# infinity_mirror_revd.net
KiCad netlist of a schematic drawn in EAGLE
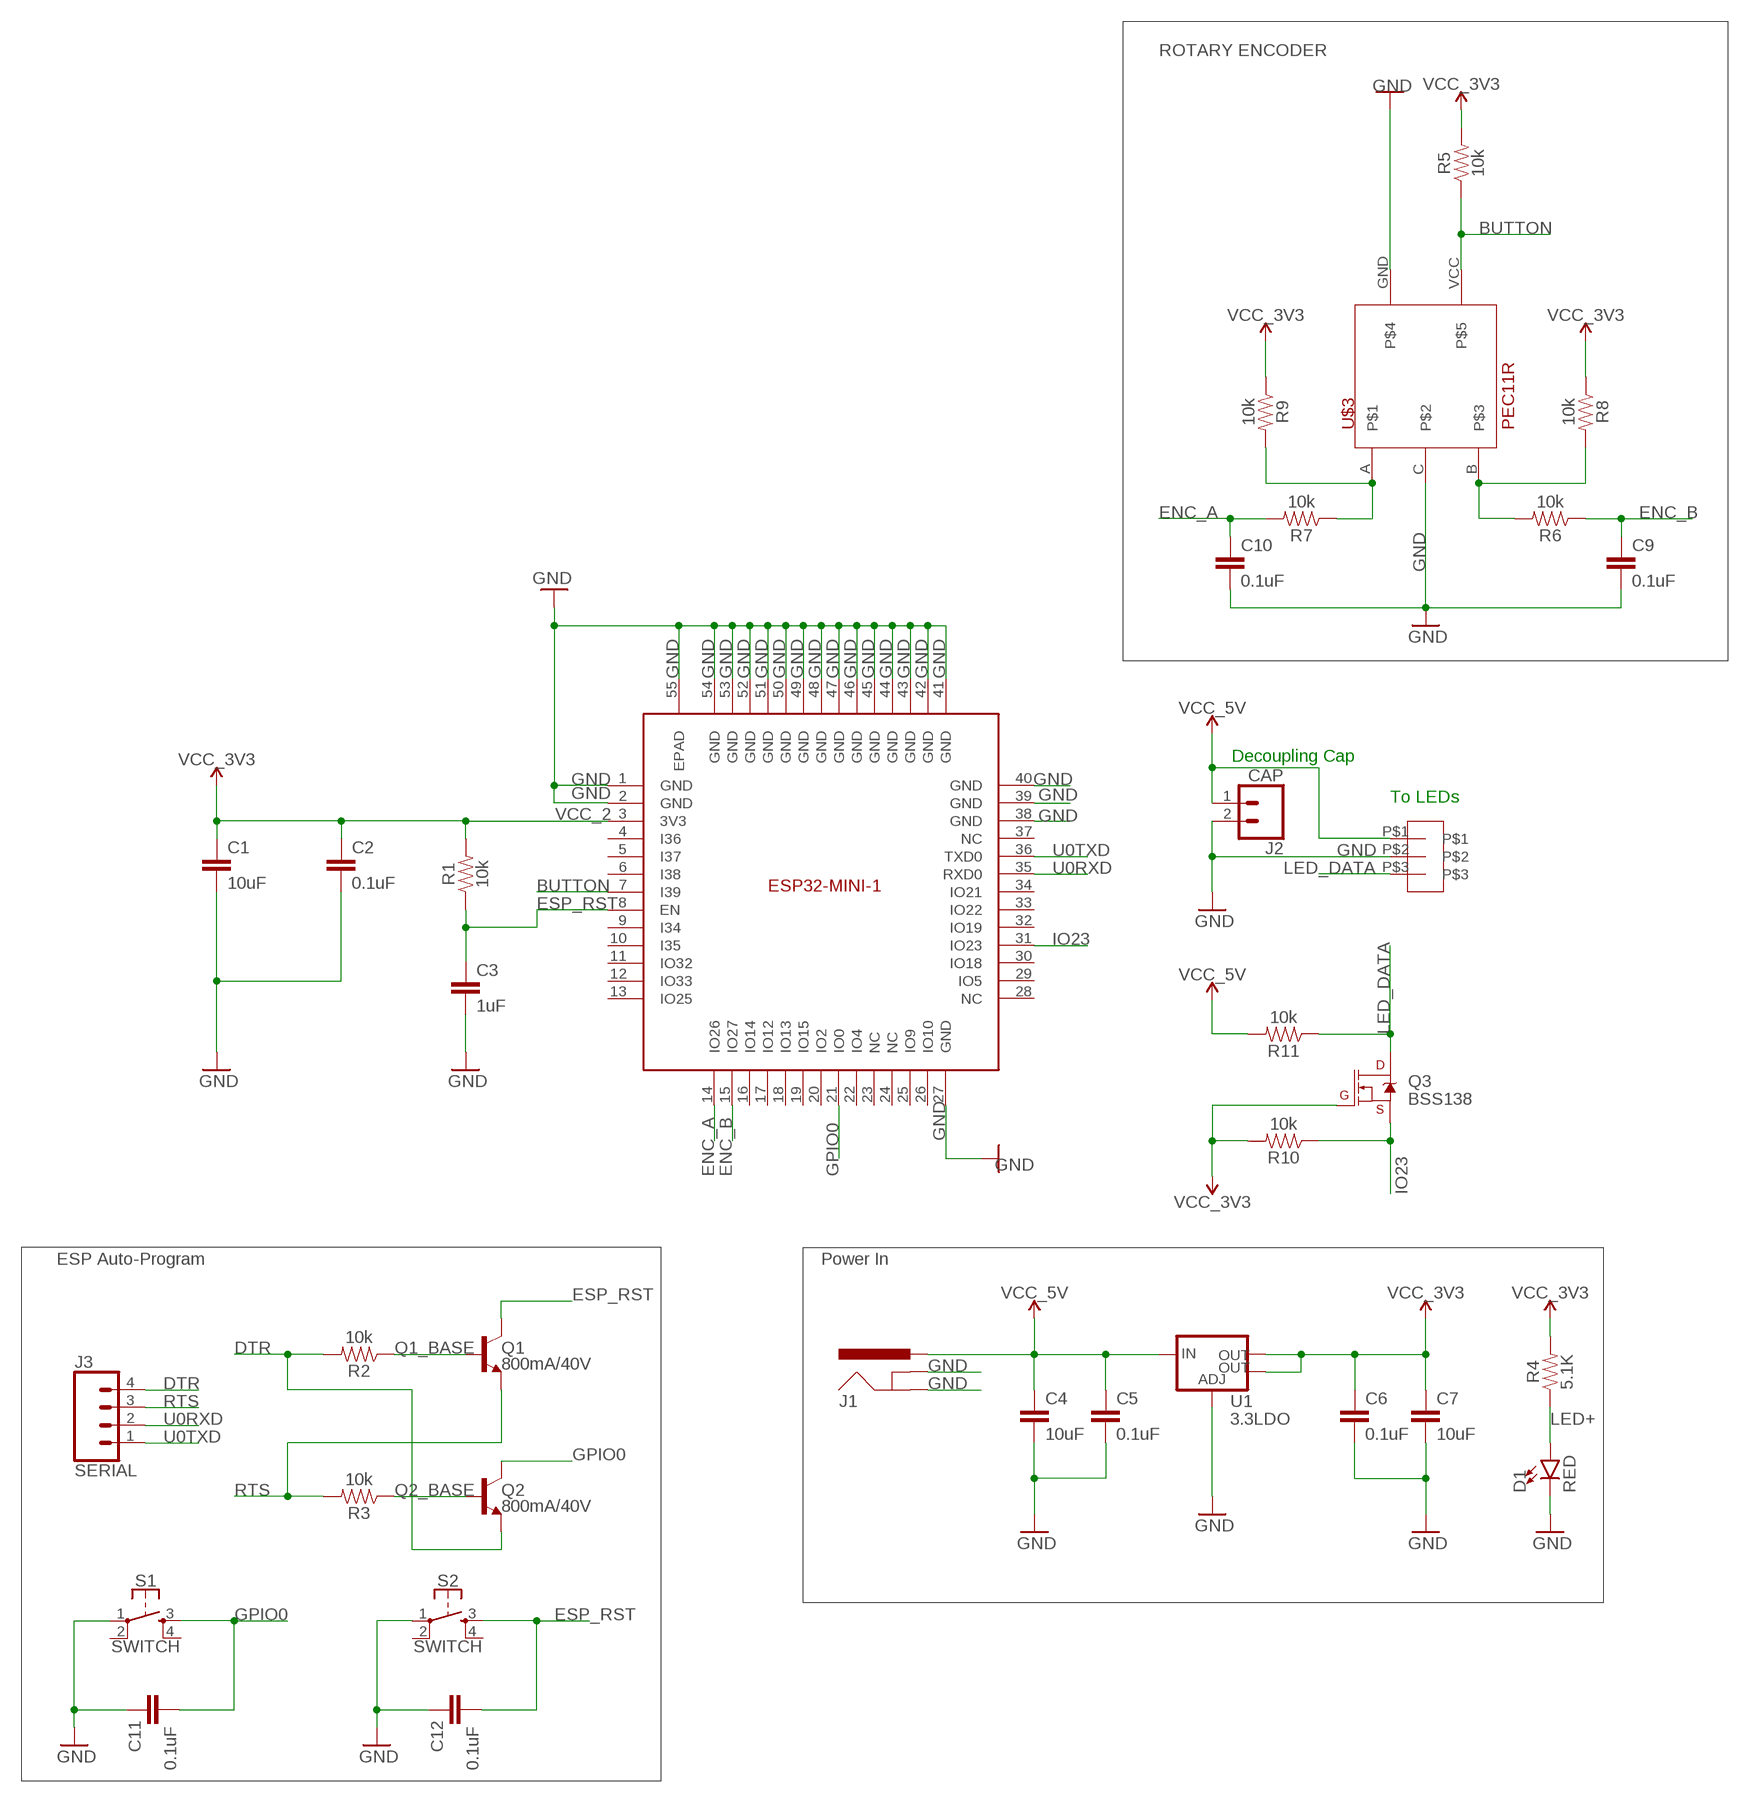
[diagram p0: schematic, sheet 1]

(export (version "E")
  (design (tool "Eeschema 10.0.6"))
  (components
    (comp (ref "C1")
      (value "10uF")
      (footprint "eagle-import:0805")
      (libsource (lib "eagle-import") (part "CAPACITOR"))
    )
    (comp (ref "C2")
      (value "0.1uF")
      (footprint "eagle-import:0805")
      (libsource (lib "eagle-import") (part "CAPACITOR"))
    )
    (comp (ref "C3")
      (value "1uF")
      (footprint "eagle-import:0805")
      (libsource (lib "eagle-import") (part "CAPACITOR"))
    )
    (comp (ref "C4")
      (value "10uF")
      (footprint "eagle-import:0805")
      (libsource (lib "eagle-import") (part "CAPACITOR"))
    )
    (comp (ref "C5")
      (value "0.1uF")
      (footprint "eagle-import:0805")
      (libsource (lib "eagle-import") (part "CAPACITOR"))
    )
    (comp (ref "C6")
      (value "0.1uF")
      (footprint "eagle-import:0805")
      (libsource (lib "eagle-import") (part "CAPACITOR"))
    )
    (comp (ref "C7")
      (value "10uF")
      (footprint "eagle-import:0805")
      (libsource (lib "eagle-import") (part "CAPACITOR"))
    )
    (comp (ref "C9")
      (value "0.1uF")
      (footprint "eagle-import:0805")
      (libsource (lib "eagle-import") (part "CAPACITOR"))
    )
    (comp (ref "C10")
      (value "0.1uF")
      (footprint "eagle-import:0805")
      (libsource (lib "eagle-import") (part "CAPACITOR"))
    )
    (comp (ref "C11")
      (value "0.1uF")
      (footprint "eagle-import:0805")
      (libsource (lib "eagle-import") (part "CAPACITOR"))
    )
    (comp (ref "C12")
      (value "0.1uF")
      (footprint "eagle-import:0805")
      (libsource (lib "eagle-import") (part "CAPACITOR"))
    )
    (comp (ref "D1")
      (value "RED")
      (footprint "eagle-import:LED-1206")
      (libsource (lib "eagle-import") (part "LED-RED1206"))
    )
    (comp (ref "J1")
      (value "POWER_JACKPTH_BREAD")
      (footprint "eagle-import:POWER_JACK_PTH_BREAD")
      (libsource (lib "eagle-import") (part "POWER_JACKPTH_BREAD"))
    )
    (comp (ref "J2")
      (value "CAP")
      (footprint "eagle-import:1X02")
      (libsource (lib "eagle-import") (part "CONN_02"))
    )
    (comp (ref "J3")
      (value "SERIAL")
      (footprint "eagle-import:1X04")
      (libsource (lib "eagle-import") (part "CONN_04"))
    )
    (comp (ref "Q1")
      (value "800mA/40V")
      (footprint "eagle-import:SOT23-3")
      (libsource (lib "eagle-import") (part "TRANS_NPN-MMBT2222AL"))
    )
    (comp (ref "Q2")
      (value "800mA/40V")
      (footprint "eagle-import:SOT23-3")
      (libsource (lib "eagle-import") (part "TRANS_NPN-MMBT2222AL"))
    )
    (comp (ref "Q3")
      (value "BSS138")
      (footprint "eagle-import:SOT23-3")
      (libsource (lib "eagle-import") (part "MOSFET-NCH-BSS138"))
    )
    (comp (ref "R1")
      (value "10k")
      (footprint "eagle-import:0805")
      (libsource (lib "eagle-import") (part "RESISTOR"))
    )
    (comp (ref "R2")
      (value "10k")
      (footprint "eagle-import:0805")
      (libsource (lib "eagle-import") (part "RESISTOR"))
    )
    (comp (ref "R3")
      (value "10k")
      (footprint "eagle-import:0805")
      (libsource (lib "eagle-import") (part "RESISTOR"))
    )
    (comp (ref "R4")
      (value "5.1K")
      (footprint "eagle-import:0805")
      (libsource (lib "eagle-import") (part "RESISTOR"))
    )
    (comp (ref "R5")
      (value "10k")
      (footprint "eagle-import:0805")
      (libsource (lib "eagle-import") (part "RESISTOR"))
    )
    (comp (ref "R6")
      (value "10k")
      (footprint "eagle-import:0805")
      (libsource (lib "eagle-import") (part "RESISTOR"))
    )
    (comp (ref "R7")
      (value "10k")
      (footprint "eagle-import:0805")
      (libsource (lib "eagle-import") (part "RESISTOR"))
    )
    (comp (ref "R8")
      (value "10k")
      (footprint "eagle-import:0805")
      (libsource (lib "eagle-import") (part "RESISTOR"))
    )
    (comp (ref "R9")
      (value "10k")
      (footprint "eagle-import:0805")
      (libsource (lib "eagle-import") (part "RESISTOR"))
    )
    (comp (ref "R10")
      (value "10k")
      (footprint "eagle-import:0805")
      (libsource (lib "eagle-import") (part "RESISTOR"))
    )
    (comp (ref "R11")
      (value "10k")
      (footprint "eagle-import:0805")
      (libsource (lib "eagle-import") (part "RESISTOR"))
    )
    (comp (ref "S1")
      (value "SWITCH")
      (footprint "eagle-import:TACTILE_SWITCH_SMD_5.2MM")
      (libsource (lib "eagle-import") (part "MOMENTARY-SWITCH-SPST-2-SMD-5.2MM-TALL"))
    )
    (comp (ref "S2")
      (value "SWITCH")
      (footprint "eagle-import:TACTILE_SWITCH_SMD_5.2MM")
      (libsource (lib "eagle-import") (part "MOMENTARY-SWITCH-SPST-2-SMD-5.2MM-TALL"))
    )
    (comp (ref "U$1")
      (value "ESP32-MINI-1-N4")
      (footprint "eagle-import:ESP32-MINI-1-N4")
      (libsource (lib "eagle-import") (part "ESP32-MINI-1-N4"))
    )
    (comp (ref "U$2")
      (value "3-PIN-JST")
      (footprint "eagle-import:3-PIN-JST")
      (libsource (lib "eagle-import") (part "3-PIN-JST"))
    )
    (comp (ref "U$3")
      (value "PEC11R")
      (footprint "eagle-import:PEC11R-4320F-S0012")
      (libsource (lib "eagle-import") (part "PEC11R_ROTARY_ENCODER"))
    )
    (comp (ref "U1")
      (value "3.3LDO")
      (footprint "eagle-import:SOT223")
      (libsource (lib "eagle-import") (part "V_REG_LM1117SOT223"))
    )
  )
  (nets
    (net (code "1") (name "/BUTTON") (class "Default")
      (node (ref "R5") (pin "1") (pinfunction "1_1") (pintype "passive"))
      (node (ref "U$1") (pin "7") (pinfunction "I39_7") (pintype "bidirectional"))
      (node (ref "U$3") (pin "VCC") (pinfunction "P$5_VCC") (pintype "bidirectional"))
    )
    (net (code "2") (name "/DTR") (class "Default")
      (node (ref "J3") (pin "4") (pinfunction "4_4") (pintype "passive"))
      (node (ref "Q2") (pin "2") (pinfunction "E_2") (pintype "passive"))
      (node (ref "R2") (pin "2") (pinfunction "2_2") (pintype "passive"))
    )
    (net (code "3") (name "/ENC_A") (class "Default")
      (node (ref "C10") (pin "1") (pinfunction "1_1") (pintype "passive"))
      (node (ref "R7") (pin "2") (pinfunction "2_2") (pintype "passive"))
      (node (ref "U$1") (pin "14") (pinfunction "IO26_14") (pintype "bidirectional"))
    )
    (net (code "4") (name "/ENC_B") (class "Default")
      (node (ref "C9") (pin "1") (pinfunction "1_1") (pintype "passive"))
      (node (ref "R6") (pin "1") (pinfunction "1_1") (pintype "passive"))
      (node (ref "U$1") (pin "15") (pinfunction "IO27_15") (pintype "bidirectional"))
    )
    (net (code "5") (name "/ESP_RST") (class "Default")
      (node (ref "C12") (pin "2") (pinfunction "2_2") (pintype "passive"))
      (node (ref "C3") (pin "1") (pinfunction "1_1") (pintype "passive"))
      (node (ref "Q1") (pin "3") (pinfunction "C_3") (pintype "passive"))
      (node (ref "R1") (pin "1") (pinfunction "1_1") (pintype "passive"))
      (node (ref "S2") (pin "3") (pinfunction "3_3") (pintype "passive"))
      (node (ref "U$1") (pin "8") (pinfunction "EN_8") (pintype "bidirectional"))
    )
    (net (code "6") (name "/GPIO0") (class "Default")
      (node (ref "C11") (pin "2") (pinfunction "2_2") (pintype "passive"))
      (node (ref "Q2") (pin "3") (pinfunction "C_3") (pintype "passive"))
      (node (ref "S1") (pin "3") (pinfunction "3_3") (pintype "passive"))
      (node (ref "U$1") (pin "21") (pinfunction "IO0_21") (pintype "bidirectional"))
    )
    (net (code "7") (name "/IO23") (class "Default")
      (node (ref "Q3") (pin "2") (pinfunction "S_2") (pintype "bidirectional"))
      (node (ref "R10") (pin "1") (pinfunction "1_1") (pintype "passive"))
      (node (ref "U$1") (pin "31") (pinfunction "IO23_31") (pintype "bidirectional"))
    )
    (net (code "8") (name "/LED+") (class "Default")
      (node (ref "D1") (pin "A") (pinfunction "A_A") (pintype "passive"))
      (node (ref "R4") (pin "1") (pinfunction "1_1") (pintype "passive"))
    )
    (net (code "9") (name "/LED_DATA") (class "Default")
      (node (ref "Q3") (pin "3") (pinfunction "D_3") (pintype "bidirectional"))
      (node (ref "R11") (pin "1") (pinfunction "1_1") (pintype "passive"))
      (node (ref "U$2") (pin "P$3") (pinfunction "P$3_P$3") (pintype "bidirectional"))
    )
    (net (code "10") (name "/Q1_BASE") (class "Default")
      (node (ref "Q1") (pin "1") (pinfunction "B_1") (pintype "passive"))
      (node (ref "R2") (pin "1") (pinfunction "1_1") (pintype "passive"))
    )
    (net (code "11") (name "/Q2_BASE") (class "Default")
      (node (ref "Q2") (pin "1") (pinfunction "B_1") (pintype "passive"))
      (node (ref "R3") (pin "1") (pinfunction "1_1") (pintype "passive"))
    )
    (net (code "12") (name "/RTS") (class "Default")
      (node (ref "J3") (pin "3") (pinfunction "3_3") (pintype "passive"))
      (node (ref "Q1") (pin "2") (pinfunction "E_2") (pintype "passive"))
      (node (ref "R3") (pin "2") (pinfunction "2_2") (pintype "passive"))
    )
    (net (code "13") (name "/U0RXD") (class "Default")
      (node (ref "J3") (pin "2") (pinfunction "2_2") (pintype "passive"))
      (node (ref "U$1") (pin "35") (pinfunction "RXD0_35") (pintype "bidirectional"))
    )
    (net (code "14") (name "/U0TXD") (class "Default")
      (node (ref "J3") (pin "1") (pinfunction "1_1") (pintype "passive"))
      (node (ref "U$1") (pin "36") (pinfunction "TXD0_36") (pintype "bidirectional"))
    )
    (net (code "15") (name "GND") (class "Default")
      (node (ref "C1") (pin "2") (pinfunction "2_2") (pintype "passive"))
      (node (ref "C10") (pin "2") (pinfunction "2_2") (pintype "passive"))
      (node (ref "C11") (pin "1") (pinfunction "1_1") (pintype "passive"))
      (node (ref "C12") (pin "1") (pinfunction "1_1") (pintype "passive"))
      (node (ref "C2") (pin "2") (pinfunction "2_2") (pintype "passive"))
      (node (ref "C3") (pin "2") (pinfunction "2_2") (pintype "passive"))
      (node (ref "C4") (pin "2") (pinfunction "2_2") (pintype "passive"))
      (node (ref "C5") (pin "2") (pinfunction "2_2") (pintype "passive"))
      (node (ref "C6") (pin "2") (pinfunction "2_2") (pintype "passive"))
      (node (ref "C7") (pin "2") (pinfunction "2_2") (pintype "passive"))
      (node (ref "C9") (pin "2") (pinfunction "2_2") (pintype "passive"))
      (node (ref "D1") (pin "C") (pinfunction "C_C") (pintype "passive"))
      (node (ref "J1") (pin "GND") (pinfunction "GND_GND") (pintype "bidirectional"))
      (node (ref "J1") (pin "GNDBREAK") (pinfunction "GNDBREAK_GNDBREAK") (pintype "bidirectional"))
      (node (ref "J2") (pin "2") (pinfunction "2_2") (pintype "passive"))
      (node (ref "S1") (pin "1") (pinfunction "1_1") (pintype "passive"))
      (node (ref "S2") (pin "1") (pinfunction "1_1") (pintype "passive"))
      (node (ref "U$1") (pin "1") (pinfunction "GND_1") (pintype "bidirectional"))
      (node (ref "U$1") (pin "2") (pinfunction "GND_2") (pintype "bidirectional"))
      (node (ref "U$1") (pin "27") (pinfunction "GND_27") (pintype "bidirectional"))
      (node (ref "U$1") (pin "38") (pinfunction "GND_38") (pintype "bidirectional"))
      (node (ref "U$1") (pin "39") (pinfunction "GND_39") (pintype "bidirectional"))
      (node (ref "U$1") (pin "40") (pinfunction "GND_40") (pintype "bidirectional"))
      (node (ref "U$1") (pin "41") (pinfunction "GND_41") (pintype "bidirectional"))
      (node (ref "U$1") (pin "42") (pinfunction "GND_42") (pintype "bidirectional"))
      (node (ref "U$1") (pin "43") (pinfunction "GND_43") (pintype "bidirectional"))
      (node (ref "U$1") (pin "44") (pinfunction "GND_44") (pintype "bidirectional"))
      (node (ref "U$1") (pin "45") (pinfunction "GND_45") (pintype "bidirectional"))
      (node (ref "U$1") (pin "46") (pinfunction "GND_46") (pintype "bidirectional"))
      (node (ref "U$1") (pin "47") (pinfunction "GND_47") (pintype "bidirectional"))
      (node (ref "U$1") (pin "48") (pinfunction "GND_48") (pintype "bidirectional"))
      (node (ref "U$1") (pin "49") (pinfunction "GND_49") (pintype "bidirectional"))
      (node (ref "U$1") (pin "50") (pinfunction "GND_50") (pintype "bidirectional"))
      (node (ref "U$1") (pin "51") (pinfunction "GND_51") (pintype "bidirectional"))
      (node (ref "U$1") (pin "52") (pinfunction "GND_52") (pintype "bidirectional"))
      (node (ref "U$1") (pin "53") (pinfunction "GND_53") (pintype "bidirectional"))
      (node (ref "U$1") (pin "54") (pinfunction "GND_54") (pintype "bidirectional"))
      (node (ref "U$1") (pin "55") (pinfunction "EPAD_55") (pintype "bidirectional"))
      (node (ref "U$2") (pin "P$2") (pinfunction "P$2_P$2") (pintype "bidirectional"))
      (node (ref "U$3") (pin "C") (pinfunction "P$2_C") (pintype "bidirectional"))
      (node (ref "U$3") (pin "GND") (pinfunction "P$4_GND") (pintype "bidirectional"))
      (node (ref "U1") (pin "1") (pinfunction "ADJ_1") (pintype "input"))
    )
    (net (code "16") (name "Net-(U$3-P$1)") (class "Default")
      (node (ref "R7") (pin "1") (pinfunction "1_1") (pintype "passive"))
      (node (ref "R9") (pin "2") (pinfunction "2_2") (pintype "passive"))
      (node (ref "U$3") (pin "A") (pinfunction "P$1_A") (pintype "bidirectional"))
    )
    (net (code "17") (name "Net-(U$3-P$3)") (class "Default")
      (node (ref "R6") (pin "2") (pinfunction "2_2") (pintype "passive"))
      (node (ref "R8") (pin "2") (pinfunction "2_2") (pintype "passive"))
      (node (ref "U$3") (pin "B") (pinfunction "P$3_B") (pintype "bidirectional"))
    )
    (net (code "18") (name "VCC_3V3") (class "Default")
      (node (ref "C1") (pin "1") (pinfunction "1_1") (pintype "passive"))
      (node (ref "C2") (pin "1") (pinfunction "1_1") (pintype "passive"))
      (node (ref "C6") (pin "1") (pinfunction "1_1") (pintype "passive"))
      (node (ref "C7") (pin "1") (pinfunction "1_1") (pintype "passive"))
      (node (ref "Q3") (pin "1") (pinfunction "G_1") (pintype "bidirectional"))
      (node (ref "R1") (pin "2") (pinfunction "2_2") (pintype "passive"))
      (node (ref "R10") (pin "2") (pinfunction "2_2") (pintype "passive"))
      (node (ref "R4") (pin "2") (pinfunction "2_2") (pintype "passive"))
      (node (ref "R5") (pin "2") (pinfunction "2_2") (pintype "passive"))
      (node (ref "R8") (pin "1") (pinfunction "1_1") (pintype "passive"))
      (node (ref "R9") (pin "1") (pinfunction "1_1") (pintype "passive"))
      (node (ref "U$1") (pin "3") (pinfunction "3V3_3") (pintype "bidirectional"))
      (node (ref "U1") (pin "2") (pinfunction "OUT_2") (pintype "output"))
      (node (ref "U1") (pin "4") (pinfunction "OUT_4") (pintype "output"))
    )
    (net (code "19") (name "VCC_5V") (class "Default")
      (node (ref "C4") (pin "1") (pinfunction "1_1") (pintype "passive"))
      (node (ref "C5") (pin "1") (pinfunction "1_1") (pintype "passive"))
      (node (ref "J1") (pin "PWR") (pinfunction "PWR_PWR") (pintype "bidirectional"))
      (node (ref "J2") (pin "1") (pinfunction "1_1") (pintype "passive"))
      (node (ref "R11") (pin "2") (pinfunction "2_2") (pintype "passive"))
      (node (ref "U$2") (pin "P$1") (pinfunction "P$1_P$1") (pintype "bidirectional"))
      (node (ref "U1") (pin "3") (pinfunction "IN_3") (pintype "input"))
    )
    (net (code "20") (name "unconnected-(S1-Pad2)") (class "Default")
      (node (ref "S1") (pin "2") (pinfunction "2_2") (pintype "passive"))
    )
    (net (code "21") (name "unconnected-(S1-Pad4)") (class "Default")
      (node (ref "S1") (pin "4") (pinfunction "4_4") (pintype "passive"))
    )
    (net (code "22") (name "unconnected-(S2-Pad2)") (class "Default")
      (node (ref "S2") (pin "2") (pinfunction "2_2") (pintype "passive"))
    )
    (net (code "23") (name "unconnected-(S2-Pad4)") (class "Default")
      (node (ref "S2") (pin "4") (pinfunction "4_4") (pintype "passive"))
    )
    (net (code "24") (name "unconnected-(U$1-I34-Pad9)") (class "Default")
      (node (ref "U$1") (pin "9") (pinfunction "I34_9") (pintype "bidirectional"))
    )
    (net (code "25") (name "unconnected-(U$1-I35-Pad10)") (class "Default")
      (node (ref "U$1") (pin "10") (pinfunction "I35_10") (pintype "bidirectional"))
    )
    (net (code "26") (name "unconnected-(U$1-I36-Pad4)") (class "Default")
      (node (ref "U$1") (pin "4") (pinfunction "I36_4") (pintype "bidirectional"))
    )
    (net (code "27") (name "unconnected-(U$1-I37-Pad5)") (class "Default")
      (node (ref "U$1") (pin "5") (pinfunction "I37_5") (pintype "bidirectional"))
    )
    (net (code "28") (name "unconnected-(U$1-I38-Pad6)") (class "Default")
      (node (ref "U$1") (pin "6") (pinfunction "I38_6") (pintype "bidirectional"))
    )
    (net (code "29") (name "unconnected-(U$1-IO2-Pad20)") (class "Default")
      (node (ref "U$1") (pin "20") (pinfunction "IO2_20") (pintype "bidirectional"))
    )
    (net (code "30") (name "unconnected-(U$1-IO4-Pad22)") (class "Default")
      (node (ref "U$1") (pin "22") (pinfunction "IO4_22") (pintype "bidirectional"))
    )
    (net (code "31") (name "unconnected-(U$1-IO5-Pad29)") (class "Default")
      (node (ref "U$1") (pin "29") (pinfunction "IO5_29") (pintype "bidirectional"))
    )
    (net (code "32") (name "unconnected-(U$1-IO9-Pad25)") (class "Default")
      (node (ref "U$1") (pin "25") (pinfunction "IO9_25") (pintype "bidirectional"))
    )
    (net (code "33") (name "unconnected-(U$1-IO10-Pad26)") (class "Default")
      (node (ref "U$1") (pin "26") (pinfunction "IO10_26") (pintype "bidirectional"))
    )
    (net (code "34") (name "unconnected-(U$1-IO12-Pad17)") (class "Default")
      (node (ref "U$1") (pin "17") (pinfunction "IO12_17") (pintype "bidirectional"))
    )
    (net (code "35") (name "unconnected-(U$1-IO13-Pad18)") (class "Default")
      (node (ref "U$1") (pin "18") (pinfunction "IO13_18") (pintype "bidirectional"))
    )
    (net (code "36") (name "unconnected-(U$1-IO14-Pad16)") (class "Default")
      (node (ref "U$1") (pin "16") (pinfunction "IO14_16") (pintype "bidirectional"))
    )
    (net (code "37") (name "unconnected-(U$1-IO15-Pad19)") (class "Default")
      (node (ref "U$1") (pin "19") (pinfunction "IO15_19") (pintype "bidirectional"))
    )
    (net (code "38") (name "unconnected-(U$1-IO18-Pad30)") (class "Default")
      (node (ref "U$1") (pin "30") (pinfunction "IO18_30") (pintype "bidirectional"))
    )
    (net (code "39") (name "unconnected-(U$1-IO19-Pad32)") (class "Default")
      (node (ref "U$1") (pin "32") (pinfunction "IO19_32") (pintype "bidirectional"))
    )
    (net (code "40") (name "unconnected-(U$1-IO21-Pad34)") (class "Default")
      (node (ref "U$1") (pin "34") (pinfunction "IO21_34") (pintype "bidirectional"))
    )
    (net (code "41") (name "unconnected-(U$1-IO22-Pad33)") (class "Default")
      (node (ref "U$1") (pin "33") (pinfunction "IO22_33") (pintype "bidirectional"))
    )
    (net (code "42") (name "unconnected-(U$1-IO25-Pad13)") (class "Default")
      (node (ref "U$1") (pin "13") (pinfunction "IO25_13") (pintype "bidirectional"))
    )
    (net (code "43") (name "unconnected-(U$1-IO32-Pad11)") (class "Default")
      (node (ref "U$1") (pin "11") (pinfunction "IO32_11") (pintype "bidirectional"))
    )
    (net (code "44") (name "unconnected-(U$1-IO33-Pad12)") (class "Default")
      (node (ref "U$1") (pin "12") (pinfunction "IO33_12") (pintype "bidirectional"))
    )
    (net (code "45") (name "unconnected-(U$1-NC-Pad23)") (class "Default")
      (node (ref "U$1") (pin "23") (pinfunction "NC_23") (pintype "bidirectional"))
    )
    (net (code "46") (name "unconnected-(U$1-NC-Pad24)") (class "Default")
      (node (ref "U$1") (pin "24") (pinfunction "NC_24") (pintype "bidirectional"))
    )
    (net (code "47") (name "unconnected-(U$1-NC-Pad28)") (class "Default")
      (node (ref "U$1") (pin "28") (pinfunction "NC_28") (pintype "bidirectional"))
    )
    (net (code "48") (name "unconnected-(U$1-NC-Pad37)") (class "Default")
      (node (ref "U$1") (pin "37") (pinfunction "NC_37") (pintype "bidirectional"))
    )
  )
)
